# clock.net
KiCad netlist of a schematic drawn in EAGLE
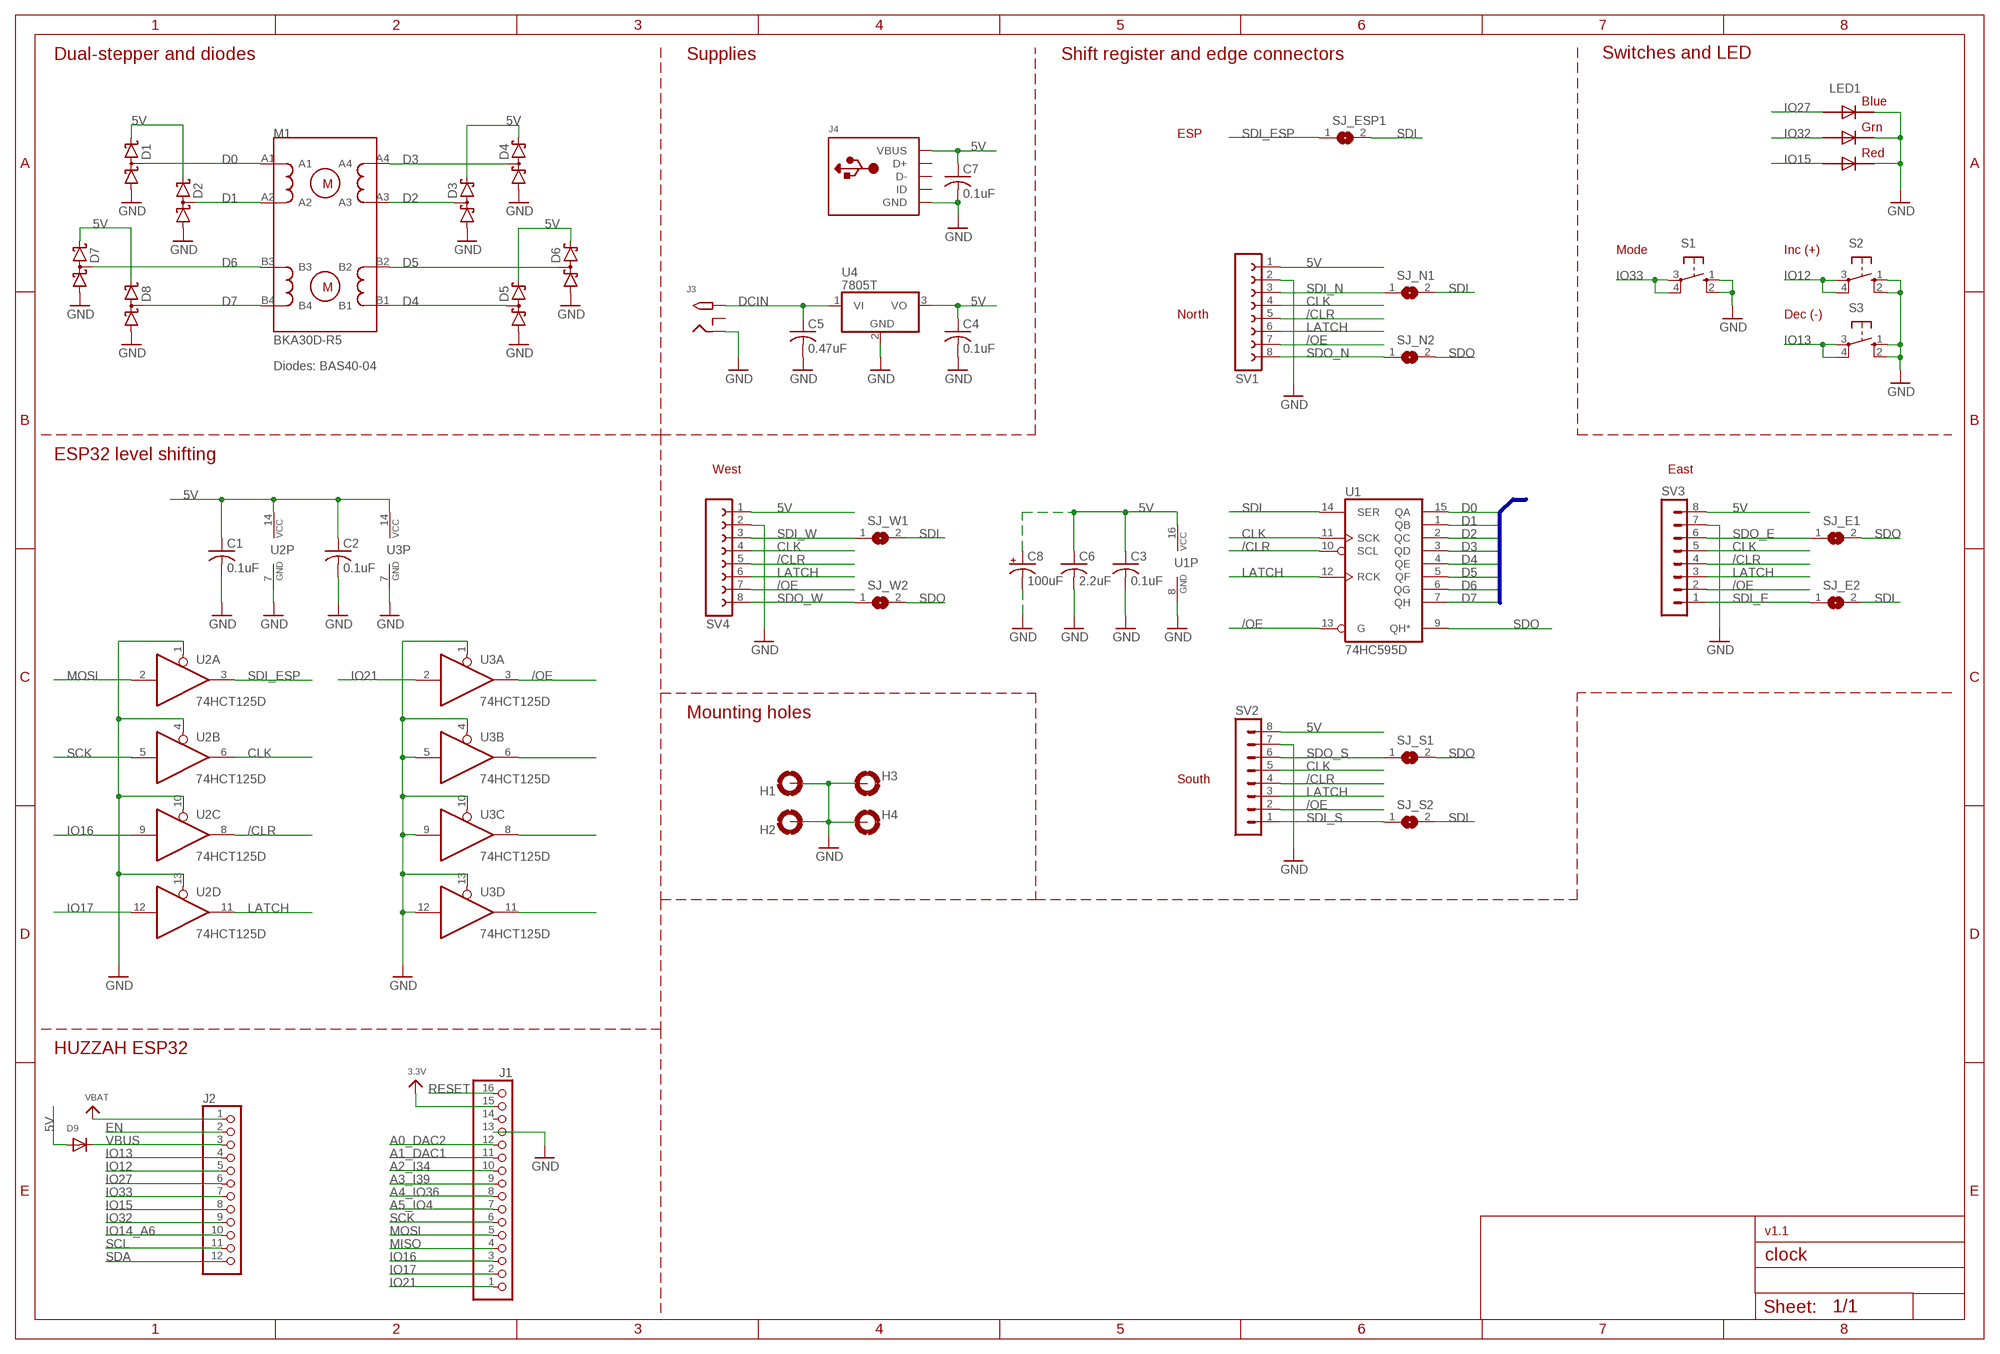
[diagram p0: schematic, sheet 1]

(export (version "E")
  (design (tool "Eeschema 10.0.6"))
  (components
    (comp (ref "C1")
      (value "0.1uF")
      (footprint "eagle-import:C0805K")
      (libsource (lib "eagle-import") (part "C-USC0805K"))
    )
    (comp (ref "C2")
      (value "0.1uF")
      (footprint "eagle-import:C0805K")
      (libsource (lib "eagle-import") (part "C-USC0805K"))
    )
    (comp (ref "C3")
      (value "0.1uF")
      (footprint "eagle-import:C0805K")
      (libsource (lib "eagle-import") (part "C-USC0805K"))
    )
    (comp (ref "C4")
      (value "0.1uF")
      (footprint "eagle-import:C0805K")
      (libsource (lib "eagle-import") (part "C-USC0805K"))
    )
    (comp (ref "C5")
      (value "0.47uF")
      (footprint "eagle-import:C0805K")
      (libsource (lib "eagle-import") (part "C-USC0805K"))
    )
    (comp (ref "C6")
      (value "2.2uF")
      (footprint "eagle-import:C0805K")
      (libsource (lib "eagle-import") (part "C-USC0805K"))
    )
    (comp (ref "C7")
      (value "0.1uF")
      (footprint "eagle-import:C0805K")
      (libsource (lib "eagle-import") (part "C-USC0805K"))
    )
    (comp (ref "C8")
      (value "100uF")
      (footprint "eagle-import:E3,5-8")
      (libsource (lib "eagle-import") (part "CPOL-USE3.5-8"))
    )
    (comp (ref "D1")
      (value "BAS40-04")
      (footprint "eagle-import:SOT23")
      (libsource (lib "eagle-import") (part "BAS40-04"))
    )
    (comp (ref "D2")
      (value "BAS40-04")
      (footprint "eagle-import:SOT23")
      (libsource (lib "eagle-import") (part "BAS40-04"))
    )
    (comp (ref "D3")
      (value "BAS40-04")
      (footprint "eagle-import:SOT23")
      (libsource (lib "eagle-import") (part "BAS40-04"))
    )
    (comp (ref "D4")
      (value "BAS40-04")
      (footprint "eagle-import:SOT23")
      (libsource (lib "eagle-import") (part "BAS40-04"))
    )
    (comp (ref "D5")
      (value "BAS40-04")
      (footprint "eagle-import:SOT23")
      (libsource (lib "eagle-import") (part "BAS40-04"))
    )
    (comp (ref "D6")
      (value "BAS40-04")
      (footprint "eagle-import:SOT23")
      (libsource (lib "eagle-import") (part "BAS40-04"))
    )
    (comp (ref "D7")
      (value "BAS40-04")
      (footprint "eagle-import:SOT23")
      (libsource (lib "eagle-import") (part "BAS40-04"))
    )
    (comp (ref "D8")
      (value "BAS40-04")
      (footprint "eagle-import:SOT23")
      (libsource (lib "eagle-import") (part "BAS40-04"))
    )
    (comp (ref "D9")
      (value "DIODEDO-1N4148")
      (footprint "eagle-import:DO-1N4148")
      (libsource (lib "eagle-import") (part "DIODEDO-1N4148"))
    )
    (comp (ref "H1")
      (value "MOUNT-PAD-ROUND3.2")
      (footprint "eagle-import:3,2-PAD")
      (libsource (lib "eagle-import") (part "MOUNT-PAD-ROUND3.2"))
    )
    (comp (ref "H2")
      (value "MOUNT-PAD-ROUND3.2")
      (footprint "eagle-import:3,2-PAD")
      (libsource (lib "eagle-import") (part "MOUNT-PAD-ROUND3.2"))
    )
    (comp (ref "H3")
      (value "MOUNT-PAD-ROUND3.2")
      (footprint "eagle-import:3,2-PAD")
      (libsource (lib "eagle-import") (part "MOUNT-PAD-ROUND3.2"))
    )
    (comp (ref "H4")
      (value "MOUNT-PAD-ROUND3.2")
      (footprint "eagle-import:3,2-PAD")
      (libsource (lib "eagle-import") (part "MOUNT-PAD-ROUND3.2"))
    )
    (comp (ref "J1")
      (value "HEADER-1X16_MIN")
      (footprint "eagle-import:1X16_ROUND_MIN")
      (libsource (lib "eagle-import") (part "HEADER-1X16_MIN"))
    )
    (comp (ref "J2")
      (value "HEADER-1X12_MIN")
      (footprint "eagle-import:1X12_ROUND_MIN")
      (libsource (lib "eagle-import") (part "HEADER-1X12_MIN"))
    )
    (comp (ref "J3")
      (value "2.1MMJACKTHM")
      (footprint "eagle-import:PJ-102A")
      (libsource (lib "eagle-import") (part "2.1MMJACKTHM"))
    )
    (comp (ref "J4")
      (value "USBMINIB")
      (footprint "eagle-import:USB-MINIB")
      (libsource (lib "eagle-import") (part "USBMINIB"))
    )
    (comp (ref "LED1")
      (value "RGBLED5050")
      (footprint "eagle-import:RGBLED5050")
      (libsource (lib "eagle-import") (part "RGBLED5050"))
    )
    (comp (ref "M1")
      (value "BKA30D-R5")
      (footprint "eagle-import:BKA30D-R5")
      (libsource (lib "eagle-import") (part "BKA30D-R5"))
    )
    (comp (ref "S1")
      (value "10-XX")
      (footprint "eagle-import:B3F-10XX")
      (fields (field (name "MPN") "B3F-1000"))
      (libsource (lib "eagle-import") (part "10-XX"))
    )
    (comp (ref "S2")
      (value "10-XX")
      (footprint "eagle-import:B3F-10XX")
      (fields (field (name "MPN") "B3F-1000"))
      (libsource (lib "eagle-import") (part "10-XX"))
    )
    (comp (ref "S3")
      (value "10-XX")
      (footprint "eagle-import:B3F-10XX")
      (fields (field (name "MPN") "B3F-1000"))
      (libsource (lib "eagle-import") (part "10-XX"))
    )
    (comp (ref "SJ_E1")
      (value "SJ")
      (footprint "eagle-import:SJ")
      (libsource (lib "eagle-import") (part "SJ"))
    )
    (comp (ref "SJ_E2")
      (value "SJ")
      (footprint "eagle-import:SJ")
      (libsource (lib "eagle-import") (part "SJ"))
    )
    (comp (ref "SJ_ESP1")
      (value "SJ")
      (footprint "eagle-import:SJ")
      (libsource (lib "eagle-import") (part "SJ"))
    )
    (comp (ref "SJ_N1")
      (value "SJ")
      (footprint "eagle-import:SJ")
      (libsource (lib "eagle-import") (part "SJ"))
    )
    (comp (ref "SJ_N2")
      (value "SJ")
      (footprint "eagle-import:SJ")
      (libsource (lib "eagle-import") (part "SJ"))
    )
    (comp (ref "SJ_S1")
      (value "SJ")
      (footprint "eagle-import:SJ")
      (libsource (lib "eagle-import") (part "SJ"))
    )
    (comp (ref "SJ_S2")
      (value "SJ")
      (footprint "eagle-import:SJ")
      (libsource (lib "eagle-import") (part "SJ"))
    )
    (comp (ref "SJ_W1")
      (value "SJ")
      (footprint "eagle-import:SJ")
      (libsource (lib "eagle-import") (part "SJ"))
    )
    (comp (ref "SJ_W2")
      (value "SJ")
      (footprint "eagle-import:SJ")
      (libsource (lib "eagle-import") (part "SJ"))
    )
    (comp (ref "SV1")
      (value "FE08W")
      (footprint "eagle-import:FE08W")
      (libsource (lib "eagle-import") (part "FE08W"))
    )
    (comp (ref "SV2")
      (value "MA08-1W")
      (footprint "eagle-import:MA08-1W")
      (libsource (lib "eagle-import") (part "MA08-1W"))
    )
    (comp (ref "SV3")
      (value "MA08-1W")
      (footprint "eagle-import:MA08-1W")
      (libsource (lib "eagle-import") (part "MA08-1W"))
    )
    (comp (ref "SV4")
      (value "FE08W")
      (footprint "eagle-import:FE08W")
      (libsource (lib "eagle-import") (part "FE08W"))
    )
    (comp (ref "U1")
      (value "74HC595D")
      (footprint "eagle-import:SO16")
      (libsource (lib "eagle-import") (part "74595DHC"))
    )
    (comp (ref "U2")
      (value "74HCT125D")
      (footprint "eagle-import:SO14")
      (libsource (lib "eagle-import") (part "74125DHCT"))
    )
    (comp (ref "U3")
      (value "74HCT125D")
      (footprint "eagle-import:SO14")
      (libsource (lib "eagle-import") (part "74125DHCT"))
    )
    (comp (ref "U4")
      (value "7805T")
      (footprint "eagle-import:TO220H")
      (libsource (lib "eagle-import") (part "78T05"))
    )
  )
  (nets
    (net (code "1") (name "/5V") (class "Default")
      (node (ref "C1") (pin "1") (pinfunction "1_1") (pintype "passive"))
      (node (ref "C2") (pin "1") (pinfunction "1_1") (pintype "passive"))
      (node (ref "C3") (pin "1") (pinfunction "1_1") (pintype "passive"))
      (node (ref "C4") (pin "1") (pinfunction "1_1") (pintype "passive"))
      (node (ref "C6") (pin "1") (pinfunction "1_1") (pintype "passive"))
      (node (ref "C7") (pin "1") (pinfunction "1_1") (pintype "passive"))
      (node (ref "C8") (pin "+") (pinfunction "+_+") (pintype "passive"))
      (node (ref "D1") (pin "2") (pinfunction "C2_2") (pintype "passive"))
      (node (ref "D2") (pin "2") (pinfunction "C2_2") (pintype "passive"))
      (node (ref "D3") (pin "2") (pinfunction "C2_2") (pintype "passive"))
      (node (ref "D4") (pin "2") (pinfunction "C2_2") (pintype "passive"))
      (node (ref "D5") (pin "2") (pinfunction "C2_2") (pintype "passive"))
      (node (ref "D6") (pin "2") (pinfunction "C2_2") (pintype "passive"))
      (node (ref "D7") (pin "2") (pinfunction "C2_2") (pintype "passive"))
      (node (ref "D8") (pin "2") (pinfunction "C2_2") (pintype "passive"))
      (node (ref "D9") (pin "A") (pinfunction "A_A") (pintype "passive"))
      (node (ref "J4") (pin "VBUS") (pinfunction "VBUS_VBUS") (pintype "power_in"))
      (node (ref "SV1") (pin "1") (pinfunction "1_1") (pintype "passive"))
      (node (ref "SV2") (pin "8") (pinfunction "8_8") (pintype "passive"))
      (node (ref "SV3") (pin "8") (pinfunction "8_8") (pintype "passive"))
      (node (ref "SV4") (pin "1") (pinfunction "1_1") (pintype "passive"))
      (node (ref "U1") (pin "16") (pinfunction "VCC_16") (pintype "power_in"))
      (node (ref "U2") (pin "14") (pinfunction "VCC_14") (pintype "power_in"))
      (node (ref "U3") (pin "14") (pinfunction "VCC_14") (pintype "power_in"))
      (node (ref "U4") (pin "3") (pinfunction "VO_3") (pintype "passive"))
    )
    (net (code "2") (name "/A0_DAC2") (class "Default")
      (node (ref "J1") (pin "12") (pinfunction "12_12") (pintype "passive"))
    )
    (net (code "3") (name "/A1_DAC1") (class "Default")
      (node (ref "J1") (pin "11") (pinfunction "11_11") (pintype "passive"))
    )
    (net (code "4") (name "/A2_I34") (class "Default")
      (node (ref "J1") (pin "10") (pinfunction "10_10") (pintype "passive"))
    )
    (net (code "5") (name "/A3_I39") (class "Default")
      (node (ref "J1") (pin "9") (pinfunction "9_9") (pintype "passive"))
    )
    (net (code "6") (name "/A4_IO36") (class "Default")
      (node (ref "J1") (pin "8") (pinfunction "8_8") (pintype "passive"))
    )
    (net (code "7") (name "/A5_IO4") (class "Default")
      (node (ref "J1") (pin "7") (pinfunction "7_7") (pintype "passive"))
    )
    (net (code "8") (name "/CLK") (class "Default")
      (node (ref "SV1") (pin "4") (pinfunction "4_4") (pintype "passive"))
      (node (ref "SV2") (pin "5") (pinfunction "5_5") (pintype "passive"))
      (node (ref "SV3") (pin "5") (pinfunction "5_5") (pintype "passive"))
      (node (ref "SV4") (pin "4") (pinfunction "4_4") (pintype "passive"))
      (node (ref "U1") (pin "11") (pinfunction "SCK_11") (pintype "input"))
      (node (ref "U2") (pin "6") (pinfunction "O_6") (pintype "tri_state"))
    )
    (net (code "9") (name "/D0") (class "Default")
      (node (ref "D1") (pin "3") (pinfunction "C1A2_3") (pintype "passive"))
      (node (ref "M1") (pin "A1") (pinfunction "A1_A1") (pintype "bidirectional"))
      (node (ref "U1") (pin "15") (pinfunction "QA_15") (pintype "tri_state"))
    )
    (net (code "10") (name "/D1") (class "Default")
      (node (ref "D2") (pin "3") (pinfunction "C1A2_3") (pintype "passive"))
      (node (ref "M1") (pin "A2") (pinfunction "A2_A2") (pintype "bidirectional"))
      (node (ref "U1") (pin "1") (pinfunction "QB_1") (pintype "tri_state"))
    )
    (net (code "11") (name "/D2") (class "Default")
      (node (ref "D3") (pin "3") (pinfunction "C1A2_3") (pintype "passive"))
      (node (ref "M1") (pin "A3") (pinfunction "A3_A3") (pintype "bidirectional"))
      (node (ref "U1") (pin "2") (pinfunction "QC_2") (pintype "tri_state"))
    )
    (net (code "12") (name "/D3") (class "Default")
      (node (ref "D4") (pin "3") (pinfunction "C1A2_3") (pintype "passive"))
      (node (ref "M1") (pin "A4") (pinfunction "A4_A4") (pintype "bidirectional"))
      (node (ref "U1") (pin "3") (pinfunction "QD_3") (pintype "tri_state"))
    )
    (net (code "13") (name "/D4") (class "Default")
      (node (ref "D5") (pin "3") (pinfunction "C1A2_3") (pintype "passive"))
      (node (ref "M1") (pin "B1") (pinfunction "B1_B1") (pintype "bidirectional"))
      (node (ref "U1") (pin "4") (pinfunction "QE_4") (pintype "tri_state"))
    )
    (net (code "14") (name "/D5") (class "Default")
      (node (ref "D6") (pin "3") (pinfunction "C1A2_3") (pintype "passive"))
      (node (ref "M1") (pin "B2") (pinfunction "B2_B2") (pintype "bidirectional"))
      (node (ref "U1") (pin "5") (pinfunction "QF_5") (pintype "tri_state"))
    )
    (net (code "15") (name "/D6") (class "Default")
      (node (ref "D7") (pin "3") (pinfunction "C1A2_3") (pintype "passive"))
      (node (ref "M1") (pin "B3") (pinfunction "B3_B3") (pintype "bidirectional"))
      (node (ref "U1") (pin "6") (pinfunction "QG_6") (pintype "tri_state"))
    )
    (net (code "16") (name "/D7") (class "Default")
      (node (ref "D8") (pin "3") (pinfunction "C1A2_3") (pintype "passive"))
      (node (ref "M1") (pin "B4") (pinfunction "B4_B4") (pintype "bidirectional"))
      (node (ref "U1") (pin "7") (pinfunction "QH_7") (pintype "tri_state"))
    )
    (net (code "17") (name "/DCIN") (class "Default")
      (node (ref "C5") (pin "1") (pinfunction "1_1") (pintype "passive"))
      (node (ref "J3") (pin "TIP") (pinfunction "TIP_TIP") (pintype "bidirectional"))
      (node (ref "U4") (pin "1") (pinfunction "VI_1") (pintype "input"))
    )
    (net (code "18") (name "/EN") (class "Default")
      (node (ref "J2") (pin "2") (pinfunction "2_2") (pintype "passive"))
    )
    (net (code "19") (name "/IO12") (class "Default")
      (node (ref "J2") (pin "5") (pinfunction "5_5") (pintype "passive"))
      (node (ref "S2") (pin "3") (pinfunction "P_3") (pintype "passive"))
      (node (ref "S2") (pin "4") (pinfunction "P1_4") (pintype "passive"))
    )
    (net (code "20") (name "/IO13") (class "Default")
      (node (ref "J2") (pin "4") (pinfunction "4_4") (pintype "passive"))
      (node (ref "S3") (pin "3") (pinfunction "P_3") (pintype "passive"))
      (node (ref "S3") (pin "4") (pinfunction "P1_4") (pintype "passive"))
    )
    (net (code "21") (name "/IO14_A6") (class "Default")
      (node (ref "J2") (pin "10") (pinfunction "10_10") (pintype "passive"))
    )
    (net (code "22") (name "/IO15") (class "Default")
      (node (ref "J2") (pin "8") (pinfunction "8_8") (pintype "passive"))
      (node (ref "LED1") (pin "2") (pinfunction "RED_A_2") (pintype "bidirectional"))
    )
    (net (code "23") (name "/IO16") (class "Default")
      (node (ref "J1") (pin "3") (pinfunction "3_3") (pintype "passive"))
      (node (ref "U2") (pin "9") (pinfunction "I_9") (pintype "input"))
    )
    (net (code "24") (name "/IO17") (class "Default")
      (node (ref "J1") (pin "2") (pinfunction "2_2") (pintype "passive"))
      (node (ref "U2") (pin "12") (pinfunction "I_12") (pintype "input"))
    )
    (net (code "25") (name "/IO21") (class "Default")
      (node (ref "J1") (pin "1") (pinfunction "1_1") (pintype "passive"))
      (node (ref "U3") (pin "2") (pinfunction "I_2") (pintype "input"))
    )
    (net (code "26") (name "/IO27") (class "Default")
      (node (ref "J2") (pin "6") (pinfunction "6_6") (pintype "passive"))
      (node (ref "LED1") (pin "3") (pinfunction "BLUE_A_3") (pintype "bidirectional"))
    )
    (net (code "27") (name "/IO32") (class "Default")
      (node (ref "J2") (pin "9") (pinfunction "9_9") (pintype "passive"))
      (node (ref "LED1") (pin "1") (pinfunction "GREEN_A_1") (pintype "bidirectional"))
    )
    (net (code "28") (name "/IO33") (class "Default")
      (node (ref "J2") (pin "7") (pinfunction "7_7") (pintype "passive"))
      (node (ref "S1") (pin "3") (pinfunction "P_3") (pintype "passive"))
      (node (ref "S1") (pin "4") (pinfunction "P1_4") (pintype "passive"))
    )
    (net (code "29") (name "/LATCH") (class "Default")
      (node (ref "SV1") (pin "6") (pinfunction "6_6") (pintype "passive"))
      (node (ref "SV2") (pin "3") (pinfunction "3_3") (pintype "passive"))
      (node (ref "SV3") (pin "3") (pinfunction "3_3") (pintype "passive"))
      (node (ref "SV4") (pin "6") (pinfunction "6_6") (pintype "passive"))
      (node (ref "U1") (pin "12") (pinfunction "RCK_12") (pintype "input"))
      (node (ref "U2") (pin "11") (pinfunction "O_11") (pintype "tri_state"))
    )
    (net (code "30") (name "/MISO") (class "Default")
      (node (ref "J1") (pin "4") (pinfunction "4_4") (pintype "passive"))
    )
    (net (code "31") (name "/MOSI") (class "Default")
      (node (ref "J1") (pin "5") (pinfunction "5_5") (pintype "passive"))
      (node (ref "U2") (pin "2") (pinfunction "I_2") (pintype "input"))
    )
    (net (code "32") (name "/RESET") (class "Default")
      (node (ref "J1") (pin "16") (pinfunction "16_16") (pintype "passive"))
    )
    (net (code "33") (name "/SCK") (class "Default")
      (node (ref "J1") (pin "6") (pinfunction "6_6") (pintype "passive"))
      (node (ref "U2") (pin "5") (pinfunction "I_5") (pintype "input"))
    )
    (net (code "34") (name "/SCL") (class "Default")
      (node (ref "J2") (pin "11") (pinfunction "11_11") (pintype "passive"))
    )
    (net (code "35") (name "/SDA") (class "Default")
      (node (ref "J2") (pin "12") (pinfunction "12_12") (pintype "passive"))
    )
    (net (code "36") (name "/SDI") (class "Default")
      (node (ref "SJ_E2") (pin "2") (pinfunction "2_2") (pintype "passive"))
      (node (ref "SJ_ESP1") (pin "2") (pinfunction "2_2") (pintype "passive"))
      (node (ref "SJ_N1") (pin "2") (pinfunction "2_2") (pintype "passive"))
      (node (ref "SJ_S2") (pin "2") (pinfunction "2_2") (pintype "passive"))
      (node (ref "SJ_W1") (pin "2") (pinfunction "2_2") (pintype "passive"))
      (node (ref "U1") (pin "14") (pinfunction "SER_14") (pintype "input"))
    )
    (net (code "37") (name "/SDI_E") (class "Default")
      (node (ref "SJ_E2") (pin "1") (pinfunction "1_1") (pintype "passive"))
      (node (ref "SV3") (pin "1") (pinfunction "1_1") (pintype "passive"))
    )
    (net (code "38") (name "/SDI_ESP") (class "Default")
      (node (ref "SJ_ESP1") (pin "1") (pinfunction "1_1") (pintype "passive"))
      (node (ref "U2") (pin "3") (pinfunction "O_3") (pintype "tri_state"))
    )
    (net (code "39") (name "/SDI_N") (class "Default")
      (node (ref "SJ_N1") (pin "1") (pinfunction "1_1") (pintype "passive"))
      (node (ref "SV1") (pin "3") (pinfunction "3_3") (pintype "passive"))
    )
    (net (code "40") (name "/SDI_S") (class "Default")
      (node (ref "SJ_S2") (pin "1") (pinfunction "1_1") (pintype "passive"))
      (node (ref "SV2") (pin "1") (pinfunction "1_1") (pintype "passive"))
    )
    (net (code "41") (name "/SDI_W") (class "Default")
      (node (ref "SJ_W1") (pin "1") (pinfunction "1_1") (pintype "passive"))
      (node (ref "SV4") (pin "3") (pinfunction "3_3") (pintype "passive"))
    )
    (net (code "42") (name "/SDO") (class "Default")
      (node (ref "SJ_E1") (pin "2") (pinfunction "2_2") (pintype "passive"))
      (node (ref "SJ_N2") (pin "2") (pinfunction "2_2") (pintype "passive"))
      (node (ref "SJ_S1") (pin "2") (pinfunction "2_2") (pintype "passive"))
      (node (ref "SJ_W2") (pin "2") (pinfunction "2_2") (pintype "passive"))
      (node (ref "U1") (pin "9") (pinfunction "QH*_9") (pintype "tri_state"))
    )
    (net (code "43") (name "/SDO_E") (class "Default")
      (node (ref "SJ_E1") (pin "1") (pinfunction "1_1") (pintype "passive"))
      (node (ref "SV3") (pin "6") (pinfunction "6_6") (pintype "passive"))
    )
    (net (code "44") (name "/SDO_N") (class "Default")
      (node (ref "SJ_N2") (pin "1") (pinfunction "1_1") (pintype "passive"))
      (node (ref "SV1") (pin "8") (pinfunction "8_8") (pintype "passive"))
    )
    (net (code "45") (name "/SDO_S") (class "Default")
      (node (ref "SJ_S1") (pin "1") (pinfunction "1_1") (pintype "passive"))
      (node (ref "SV2") (pin "6") (pinfunction "6_6") (pintype "passive"))
    )
    (net (code "46") (name "/SDO_W") (class "Default")
      (node (ref "SJ_W2") (pin "1") (pinfunction "1_1") (pintype "passive"))
      (node (ref "SV4") (pin "8") (pinfunction "8_8") (pintype "passive"))
    )
    (net (code "47") (name "/VBUS") (class "Default")
      (node (ref "D9") (pin "C") (pinfunction "C_C") (pintype "passive"))
      (node (ref "J2") (pin "3") (pinfunction "3_3") (pintype "passive"))
    )
    (net (code "48") (name "/{slash}CLR") (class "Default")
      (node (ref "SV1") (pin "5") (pinfunction "5_5") (pintype "passive"))
      (node (ref "SV2") (pin "4") (pinfunction "4_4") (pintype "passive"))
      (node (ref "SV3") (pin "4") (pinfunction "4_4") (pintype "passive"))
      (node (ref "SV4") (pin "5") (pinfunction "5_5") (pintype "passive"))
      (node (ref "U1") (pin "10") (pinfunction "SCL_10") (pintype "input"))
      (node (ref "U2") (pin "8") (pinfunction "O_8") (pintype "tri_state"))
    )
    (net (code "49") (name "/{slash}OE") (class "Default")
      (node (ref "SV1") (pin "7") (pinfunction "7_7") (pintype "passive"))
      (node (ref "SV2") (pin "2") (pinfunction "2_2") (pintype "passive"))
      (node (ref "SV3") (pin "2") (pinfunction "2_2") (pintype "passive"))
      (node (ref "SV4") (pin "7") (pinfunction "7_7") (pintype "passive"))
      (node (ref "U1") (pin "13") (pinfunction "G_13") (pintype "input"))
      (node (ref "U3") (pin "3") (pinfunction "O_3") (pintype "tri_state"))
    )
    (net (code "50") (name "3.3V") (class "Default")
      (node (ref "J1") (pin "15") (pinfunction "15_15") (pintype "passive"))
    )
    (net (code "51") (name "GND") (class "Default")
      (node (ref "C1") (pin "2") (pinfunction "2_2") (pintype "passive"))
      (node (ref "C2") (pin "2") (pinfunction "2_2") (pintype "passive"))
      (node (ref "C3") (pin "2") (pinfunction "2_2") (pintype "passive"))
      (node (ref "C4") (pin "2") (pinfunction "2_2") (pintype "passive"))
      (node (ref "C5") (pin "2") (pinfunction "2_2") (pintype "passive"))
      (node (ref "C6") (pin "2") (pinfunction "2_2") (pintype "passive"))
      (node (ref "C7") (pin "2") (pinfunction "2_2") (pintype "passive"))
      (node (ref "C8") (pin "-") (pinfunction "-_-") (pintype "passive"))
      (node (ref "D1") (pin "1") (pinfunction "A1_1") (pintype "passive"))
      (node (ref "D2") (pin "1") (pinfunction "A1_1") (pintype "passive"))
      (node (ref "D3") (pin "1") (pinfunction "A1_1") (pintype "passive"))
      (node (ref "D4") (pin "1") (pinfunction "A1_1") (pintype "passive"))
      (node (ref "D5") (pin "1") (pinfunction "A1_1") (pintype "passive"))
      (node (ref "D6") (pin "1") (pinfunction "A1_1") (pintype "passive"))
      (node (ref "D7") (pin "1") (pinfunction "A1_1") (pintype "passive"))
      (node (ref "D8") (pin "1") (pinfunction "A1_1") (pintype "passive"))
      (node (ref "H1") (pin "B3,2") (pinfunction "MOUNT_B3,2") (pintype "passive"))
      (node (ref "H2") (pin "B3,2") (pinfunction "MOUNT_B3,2") (pintype "passive"))
      (node (ref "H3") (pin "B3,2") (pinfunction "MOUNT_B3,2") (pintype "passive"))
      (node (ref "H4") (pin "B3,2") (pinfunction "MOUNT_B3,2") (pintype "passive"))
      (node (ref "J1") (pin "13") (pinfunction "13_13") (pintype "passive"))
      (node (ref "J3") (pin "RING") (pinfunction "RING_RING") (pintype "bidirectional"))
      (node (ref "J4") (pin "GND") (pinfunction "GND_GND") (pintype "power_in"))
      (node (ref "LED1") (pin "4") (pinfunction "BLUE_C_4") (pintype "bidirectional"))
      (node (ref "LED1") (pin "5") (pinfunction "RED_C_5") (pintype "bidirectional"))
      (node (ref "LED1") (pin "6") (pinfunction "GREEN_C_6") (pintype "bidirectional"))
      (node (ref "S1") (pin "1") (pinfunction "S_1") (pintype "passive"))
      (node (ref "S1") (pin "2") (pinfunction "S1_2") (pintype "passive"))
      (node (ref "S2") (pin "1") (pinfunction "S_1") (pintype "passive"))
      (node (ref "S2") (pin "2") (pinfunction "S1_2") (pintype "passive"))
      (node (ref "S3") (pin "1") (pinfunction "S_1") (pintype "passive"))
      (node (ref "S3") (pin "2") (pinfunction "S1_2") (pintype "passive"))
      (node (ref "SV1") (pin "2") (pinfunction "2_2") (pintype "passive"))
      (node (ref "SV2") (pin "7") (pinfunction "7_7") (pintype "passive"))
      (node (ref "SV3") (pin "7") (pinfunction "7_7") (pintype "passive"))
      (node (ref "SV4") (pin "2") (pinfunction "2_2") (pintype "passive"))
      (node (ref "U1") (pin "8") (pinfunction "GND_8") (pintype "power_in"))
      (node (ref "U2") (pin "1") (pinfunction "OE_1") (pintype "input"))
      (node (ref "U2") (pin "10") (pinfunction "OE_10") (pintype "input"))
      (node (ref "U2") (pin "13") (pinfunction "OE_13") (pintype "input"))
      (node (ref "U2") (pin "4") (pinfunction "OE_4") (pintype "input"))
      (node (ref "U2") (pin "7") (pinfunction "GND_7") (pintype "power_in"))
      (node (ref "U3") (pin "1") (pinfunction "OE_1") (pintype "input"))
      (node (ref "U3") (pin "10") (pinfunction "OE_10") (pintype "input"))
      (node (ref "U3") (pin "12") (pinfunction "I_12") (pintype "input"))
      (node (ref "U3") (pin "13") (pinfunction "OE_13") (pintype "input"))
      (node (ref "U3") (pin "4") (pinfunction "OE_4") (pintype "input"))
      (node (ref "U3") (pin "5") (pinfunction "I_5") (pintype "input"))
      (node (ref "U3") (pin "7") (pinfunction "GND_7") (pintype "power_in"))
      (node (ref "U3") (pin "9") (pinfunction "I_9") (pintype "input"))
      (node (ref "U4") (pin "2") (pinfunction "GND_2") (pintype "passive"))
    )
    (net (code "52") (name "VBAT") (class "Default")
      (node (ref "J2") (pin "1") (pinfunction "1_1") (pintype "passive"))
    )
    (net (code "53") (name "unconnected-(J1-Pad14)") (class "Default")
      (node (ref "J1") (pin "14") (pinfunction "14_14") (pintype "passive"))
    )
    (net (code "54") (name "unconnected-(J3-PadRING_SW)") (class "Default")
      (node (ref "J3") (pin "RING_SW") (pinfunction "RING_SW_RING_SW") (pintype "bidirectional"))
    )
    (net (code "55") (name "unconnected-(J4-PadD+)") (class "Default")
      (node (ref "J4") (pin "D+") (pinfunction "D+_D+") (pintype "bidirectional"))
    )
    (net (code "56") (name "unconnected-(J4-PadD-)") (class "Default")
      (node (ref "J4") (pin "D-") (pinfunction "D-_D-") (pintype "bidirectional"))
    )
    (net (code "57") (name "unconnected-(J4-PadID)") (class "Default")
      (node (ref "J4") (pin "ID") (pinfunction "ID_ID") (pintype "bidirectional"))
    )
    (net (code "58") (name "unconnected-(U3B-O-Pad6)") (class "Default")
      (node (ref "U3") (pin "6") (pinfunction "O_6") (pintype "tri_state"))
    )
    (net (code "59") (name "unconnected-(U3C-O-Pad8)") (class "Default")
      (node (ref "U3") (pin "8") (pinfunction "O_8") (pintype "tri_state"))
    )
    (net (code "60") (name "unconnected-(U3D-O-Pad11)") (class "Default")
      (node (ref "U3") (pin "11") (pinfunction "O_11") (pintype "tri_state"))
    )
  )
)
